# Sheet2.net
KiCad netlist of a schematic drawn in Altium Designer
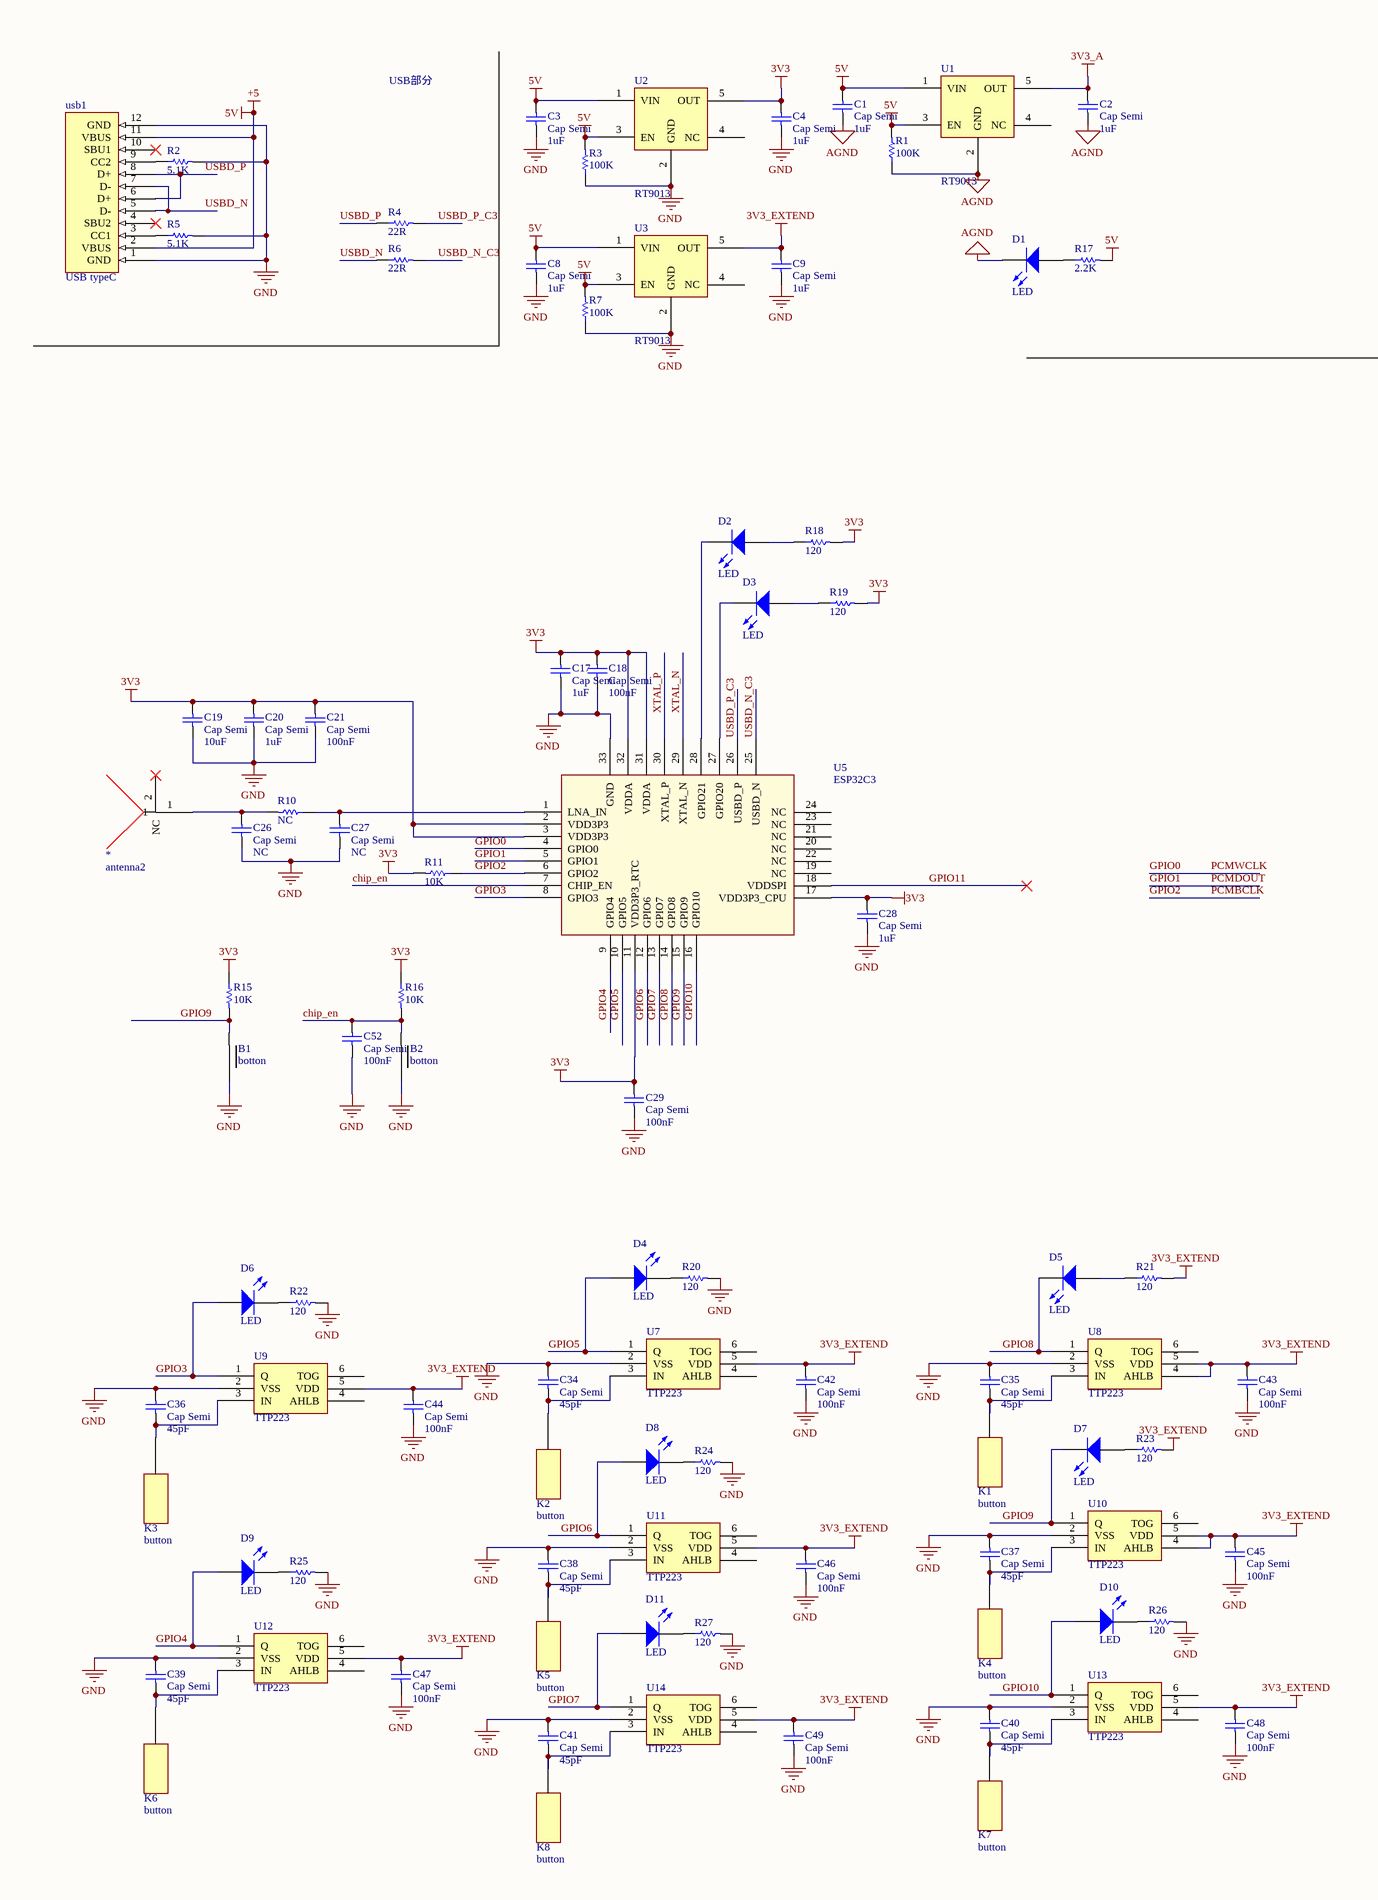
[diagram p0: Sheet2.SchDoc, left]
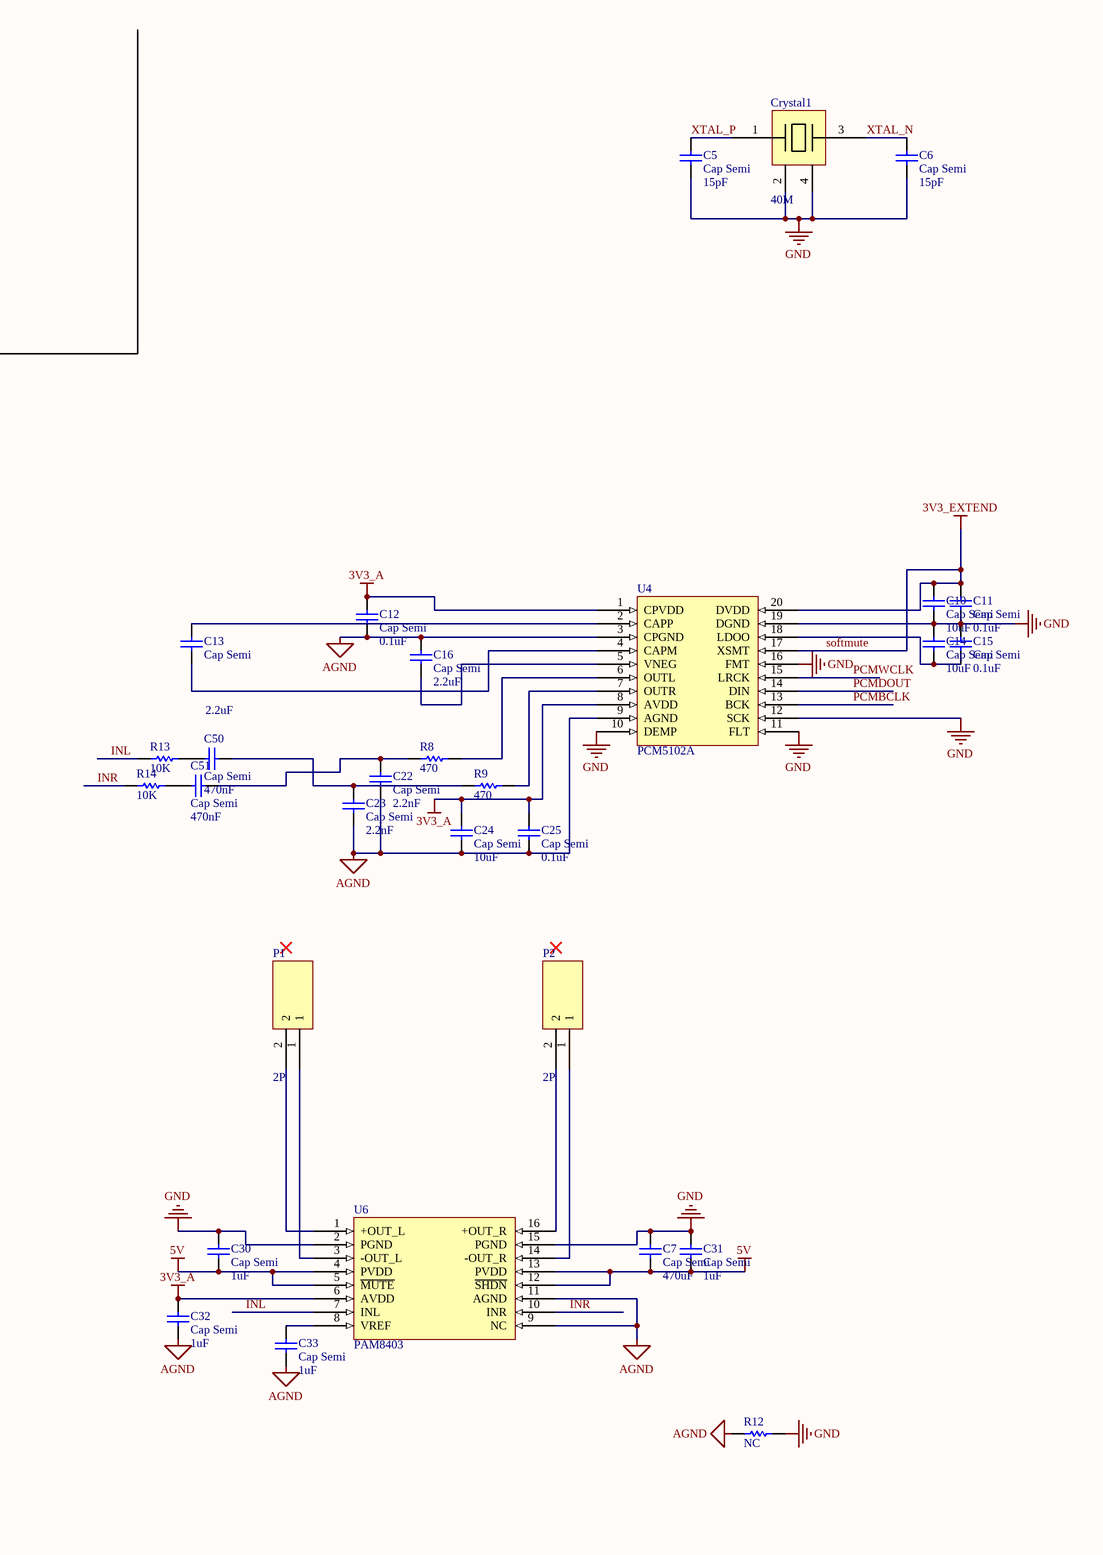
[diagram p1: Sheet2.SchDoc, right]

(export (version "E")
  (design (tool "Eeschema 10.0.6"))
  (components
    (comp (ref "*") (value "antenna2") (footprint "antana") (libsource (lib "lib_output") (part "antenna2")))
    (comp (ref "B1") (value "botton") (footprint "BOTTON_3*4") (libsource (lib "input") (part "botton")))
    (comp (ref "B2") (value "botton") (footprint "BOTTON_3*4") (libsource (lib "input") (part "botton")))
    (comp (ref "C1")
      (value "Cap Semi")
      (footprint "C1608[0603]")
      (description "Capacitor (Semiconductor SIM Model)")
      (fields (field (name "ALTIUM_VALUE") "1uF") (field (name "PUBLISHER") "Altium Limited"))
      (libsource (lib "common") (part "Cap Semi"))
    )
    (comp (ref "C2")
      (value "Cap Semi")
      (footprint "C1608[0603]")
      (description "Capacitor (Semiconductor SIM Model)")
      (fields (field (name "ALTIUM_VALUE") "1uF") (field (name "PUBLISHER") "Altium Limited"))
      (libsource (lib "common") (part "Cap Semi"))
    )
    (comp (ref "C3")
      (value "Cap Semi")
      (footprint "C1608[0603]")
      (description "Capacitor (Semiconductor SIM Model)")
      (fields (field (name "ALTIUM_VALUE") "1uF") (field (name "PUBLISHER") "Altium Limited"))
      (libsource (lib "common") (part "Cap Semi"))
    )
    (comp (ref "C4")
      (value "Cap Semi")
      (footprint "C1608[0603]")
      (description "Capacitor (Semiconductor SIM Model)")
      (fields (field (name "ALTIUM_VALUE") "1uF") (field (name "PUBLISHER") "Altium Limited"))
      (libsource (lib "common") (part "Cap Semi"))
    )
    (comp (ref "C5")
      (value "Cap Semi")
      (footprint "C1608[0603]")
      (description "Capacitor (Semiconductor SIM Model)")
      (fields (field (name "ALTIUM_VALUE") "15pF") (field (name "PUBLISHER") "Altium Limited"))
      (libsource (lib "common") (part "Cap Semi"))
    )
    (comp (ref "C6")
      (value "Cap Semi")
      (footprint "C1608[0603]")
      (description "Capacitor (Semiconductor SIM Model)")
      (fields (field (name "ALTIUM_VALUE") "15pF") (field (name "PUBLISHER") "Altium Limited"))
      (libsource (lib "common") (part "Cap Semi"))
    )
    (comp (ref "C7")
      (value "Cap Semi")
      (footprint "C1206")
      (description "Capacitor (Semiconductor SIM Model)")
      (fields (field (name "ALTIUM_VALUE") "470uF") (field (name "PUBLISHER") "Altium Limited"))
      (libsource (lib "common") (part "Cap Semi"))
    )
    (comp (ref "C8")
      (value "Cap Semi")
      (footprint "C1608[0603]")
      (description "Capacitor (Semiconductor SIM Model)")
      (fields (field (name "ALTIUM_VALUE") "1uF") (field (name "PUBLISHER") "Altium Limited"))
      (libsource (lib "common") (part "Cap Semi"))
    )
    (comp (ref "C9")
      (value "Cap Semi")
      (footprint "C1608[0603]")
      (description "Capacitor (Semiconductor SIM Model)")
      (fields (field (name "ALTIUM_VALUE") "1uF") (field (name "PUBLISHER") "Altium Limited"))
      (libsource (lib "common") (part "Cap Semi"))
    )
    (comp (ref "C10")
      (value "Cap Semi")
      (footprint "C1608[0603]")
      (description "Capacitor (Semiconductor SIM Model)")
      (fields (field (name "ALTIUM_VALUE") "10uF") (field (name "PUBLISHER") "Altium Limited"))
      (libsource (lib "common") (part "Cap Semi"))
    )
    (comp (ref "C11")
      (value "Cap Semi")
      (footprint "C1608[0603]")
      (description "Capacitor (Semiconductor SIM Model)")
      (fields (field (name "ALTIUM_VALUE") "0.1uF") (field (name "PUBLISHER") "Altium Limited"))
      (libsource (lib "common") (part "Cap Semi"))
    )
    (comp (ref "C12")
      (value "Cap Semi")
      (footprint "C1608[0603]")
      (description "Capacitor (Semiconductor SIM Model)")
      (fields (field (name "ALTIUM_VALUE") "0.1uF") (field (name "PUBLISHER") "Altium Limited"))
      (libsource (lib "common") (part "Cap Semi"))
    )
    (comp (ref "C13")
      (value "Cap Semi")
      (footprint "C1608[0603]")
      (description "Capacitor (Semiconductor SIM Model)")
      (fields (field (name "ALTIUM_VALUE") "2.2uF") (field (name "PUBLISHER") "Altium Limited"))
      (libsource (lib "common") (part "Cap Semi"))
    )
    (comp (ref "C14")
      (value "Cap Semi")
      (footprint "C1608[0603]")
      (description "Capacitor (Semiconductor SIM Model)")
      (fields (field (name "ALTIUM_VALUE") "10uF") (field (name "PUBLISHER") "Altium Limited"))
      (libsource (lib "common") (part "Cap Semi"))
    )
    (comp (ref "C15")
      (value "Cap Semi")
      (footprint "C1608[0603]")
      (description "Capacitor (Semiconductor SIM Model)")
      (fields (field (name "ALTIUM_VALUE") "0.1uF") (field (name "PUBLISHER") "Altium Limited"))
      (libsource (lib "common") (part "Cap Semi"))
    )
    (comp (ref "C16")
      (value "Cap Semi")
      (footprint "C1608[0603]")
      (description "Capacitor (Semiconductor SIM Model)")
      (fields (field (name "ALTIUM_VALUE") "2.2uF") (field (name "PUBLISHER") "Altium Limited"))
      (libsource (lib "common") (part "Cap Semi"))
    )
    (comp (ref "C17")
      (value "Cap Semi")
      (footprint "C1608[0603]")
      (description "Capacitor (Semiconductor SIM Model)")
      (fields (field (name "ALTIUM_VALUE") "1uF") (field (name "PUBLISHER") "Altium Limited"))
      (libsource (lib "common") (part "Cap Semi"))
    )
    (comp (ref "C18")
      (value "Cap Semi")
      (footprint "C1608[0603]")
      (description "Capacitor (Semiconductor SIM Model)")
      (fields (field (name "ALTIUM_VALUE") "100nF") (field (name "PUBLISHER") "Altium Limited"))
      (libsource (lib "common") (part "Cap Semi"))
    )
    (comp (ref "C19")
      (value "Cap Semi")
      (footprint "C0805")
      (description "Capacitor (Semiconductor SIM Model)")
      (fields (field (name "ALTIUM_VALUE") "10uF") (field (name "PUBLISHER") "Altium Limited"))
      (libsource (lib "common") (part "Cap Semi"))
    )
    (comp (ref "C20")
      (value "Cap Semi")
      (footprint "C1608[0603]")
      (description "Capacitor (Semiconductor SIM Model)")
      (fields (field (name "ALTIUM_VALUE") "1uF") (field (name "PUBLISHER") "Altium Limited"))
      (libsource (lib "common") (part "Cap Semi"))
    )
    (comp (ref "C21")
      (value "Cap Semi")
      (footprint "C1608[0603]")
      (description "Capacitor (Semiconductor SIM Model)")
      (fields (field (name "ALTIUM_VALUE") "100nF") (field (name "PUBLISHER") "Altium Limited"))
      (libsource (lib "common") (part "Cap Semi"))
    )
    (comp (ref "C22")
      (value "Cap Semi")
      (footprint "C1608[0603]")
      (description "Capacitor (Semiconductor SIM Model)")
      (fields (field (name "ALTIUM_VALUE") "2.2nF") (field (name "PUBLISHER") "Altium Limited"))
      (libsource (lib "common") (part "Cap Semi"))
    )
    (comp (ref "C23")
      (value "Cap Semi")
      (footprint "C1608[0603]")
      (description "Capacitor (Semiconductor SIM Model)")
      (fields (field (name "ALTIUM_VALUE") "2.2nF") (field (name "PUBLISHER") "Altium Limited"))
      (libsource (lib "common") (part "Cap Semi"))
    )
    (comp (ref "C24")
      (value "Cap Semi")
      (footprint "C1608[0603]")
      (description "Capacitor (Semiconductor SIM Model)")
      (fields (field (name "ALTIUM_VALUE") "10uF") (field (name "PUBLISHER") "Altium Limited"))
      (libsource (lib "common") (part "Cap Semi"))
    )
    (comp (ref "C25")
      (value "Cap Semi")
      (footprint "C1608[0603]")
      (description "Capacitor (Semiconductor SIM Model)")
      (fields (field (name "ALTIUM_VALUE") "0.1uF") (field (name "PUBLISHER") "Altium Limited"))
      (libsource (lib "common") (part "Cap Semi"))
    )
    (comp (ref "C26")
      (value "Cap Semi")
      (footprint "C1608[0603]")
      (description "Capacitor (Semiconductor SIM Model)")
      (fields (field (name "ALTIUM_VALUE") "NC") (field (name "PUBLISHER") "Altium Limited"))
      (libsource (lib "common") (part "Cap Semi"))
    )
    (comp (ref "C27")
      (value "Cap Semi")
      (footprint "C1608[0603]")
      (description "Capacitor (Semiconductor SIM Model)")
      (fields (field (name "ALTIUM_VALUE") "NC") (field (name "PUBLISHER") "Altium Limited"))
      (libsource (lib "common") (part "Cap Semi"))
    )
    (comp (ref "C28")
      (value "Cap Semi")
      (footprint "C1608[0603]")
      (description "Capacitor (Semiconductor SIM Model)")
      (fields (field (name "ALTIUM_VALUE") "1uF") (field (name "PUBLISHER") "Altium Limited"))
      (libsource (lib "common") (part "Cap Semi"))
    )
    (comp (ref "C29")
      (value "Cap Semi")
      (footprint "C1608[0603]")
      (description "Capacitor (Semiconductor SIM Model)")
      (fields (field (name "ALTIUM_VALUE") "100nF") (field (name "PUBLISHER") "Altium Limited"))
      (libsource (lib "common") (part "Cap Semi"))
    )
    (comp (ref "C30")
      (value "Cap Semi")
      (footprint "C1608[0603]")
      (description "Capacitor (Semiconductor SIM Model)")
      (fields (field (name "ALTIUM_VALUE") "1uF") (field (name "PUBLISHER") "Altium Limited"))
      (libsource (lib "common") (part "Cap Semi"))
    )
    (comp (ref "C31")
      (value "Cap Semi")
      (footprint "C1608[0603]")
      (description "Capacitor (Semiconductor SIM Model)")
      (fields (field (name "ALTIUM_VALUE") "1uF") (field (name "PUBLISHER") "Altium Limited"))
      (libsource (lib "common") (part "Cap Semi"))
    )
    (comp (ref "C32")
      (value "Cap Semi")
      (footprint "C1608[0603]")
      (description "Capacitor (Semiconductor SIM Model)")
      (fields (field (name "ALTIUM_VALUE") "1uF") (field (name "PUBLISHER") "Altium Limited"))
      (libsource (lib "common") (part "Cap Semi"))
    )
    (comp (ref "C33")
      (value "Cap Semi")
      (footprint "C1608[0603]")
      (description "Capacitor (Semiconductor SIM Model)")
      (fields (field (name "ALTIUM_VALUE") "1uF") (field (name "PUBLISHER") "Altium Limited"))
      (libsource (lib "common") (part "Cap Semi"))
    )
    (comp (ref "C34")
      (value "Cap Semi")
      (footprint "C1608[0603]")
      (description "Capacitor (Semiconductor SIM Model)")
      (fields (field (name "ALTIUM_VALUE") "45pF") (field (name "PUBLISHER") "Altium Limited"))
      (libsource (lib "common") (part "Cap Semi"))
    )
    (comp (ref "C35")
      (value "Cap Semi")
      (footprint "C1608[0603]")
      (description "Capacitor (Semiconductor SIM Model)")
      (fields (field (name "ALTIUM_VALUE") "45pF") (field (name "PUBLISHER") "Altium Limited"))
      (libsource (lib "common") (part "Cap Semi"))
    )
    (comp (ref "C36")
      (value "Cap Semi")
      (footprint "C1608[0603]")
      (description "Capacitor (Semiconductor SIM Model)")
      (fields (field (name "ALTIUM_VALUE") "45pF") (field (name "PUBLISHER") "Altium Limited"))
      (libsource (lib "common") (part "Cap Semi"))
    )
    (comp (ref "C37")
      (value "Cap Semi")
      (footprint "C1608[0603]")
      (description "Capacitor (Semiconductor SIM Model)")
      (fields (field (name "ALTIUM_VALUE") "45pF") (field (name "PUBLISHER") "Altium Limited"))
      (libsource (lib "common") (part "Cap Semi"))
    )
    (comp (ref "C38")
      (value "Cap Semi")
      (footprint "C1608[0603]")
      (description "Capacitor (Semiconductor SIM Model)")
      (fields (field (name "ALTIUM_VALUE") "45pF") (field (name "PUBLISHER") "Altium Limited"))
      (libsource (lib "common") (part "Cap Semi"))
    )
    (comp (ref "C39")
      (value "Cap Semi")
      (footprint "C1608[0603]")
      (description "Capacitor (Semiconductor SIM Model)")
      (fields (field (name "ALTIUM_VALUE") "45pF") (field (name "PUBLISHER") "Altium Limited"))
      (libsource (lib "common") (part "Cap Semi"))
    )
    (comp (ref "C40")
      (value "Cap Semi")
      (footprint "C1608[0603]")
      (description "Capacitor (Semiconductor SIM Model)")
      (fields (field (name "ALTIUM_VALUE") "45pF") (field (name "PUBLISHER") "Altium Limited"))
      (libsource (lib "common") (part "Cap Semi"))
    )
    (comp (ref "C41")
      (value "Cap Semi")
      (footprint "C1608[0603]")
      (description "Capacitor (Semiconductor SIM Model)")
      (fields (field (name "ALTIUM_VALUE") "45pF") (field (name "PUBLISHER") "Altium Limited"))
      (libsource (lib "common") (part "Cap Semi"))
    )
    (comp (ref "C42")
      (value "Cap Semi")
      (footprint "C1608[0603]")
      (description "Capacitor (Semiconductor SIM Model)")
      (fields (field (name "ALTIUM_VALUE") "100nF") (field (name "PUBLISHER") "Altium Limited"))
      (libsource (lib "common") (part "Cap Semi"))
    )
    (comp (ref "C43")
      (value "Cap Semi")
      (footprint "C1608[0603]")
      (description "Capacitor (Semiconductor SIM Model)")
      (fields (field (name "ALTIUM_VALUE") "100nF") (field (name "PUBLISHER") "Altium Limited"))
      (libsource (lib "common") (part "Cap Semi"))
    )
    (comp (ref "C44")
      (value "Cap Semi")
      (footprint "C1608[0603]")
      (description "Capacitor (Semiconductor SIM Model)")
      (fields (field (name "ALTIUM_VALUE") "100nF") (field (name "PUBLISHER") "Altium Limited"))
      (libsource (lib "common") (part "Cap Semi"))
    )
    (comp (ref "C45")
      (value "Cap Semi")
      (footprint "C1608[0603]")
      (description "Capacitor (Semiconductor SIM Model)")
      (fields (field (name "ALTIUM_VALUE") "100nF") (field (name "PUBLISHER") "Altium Limited"))
      (libsource (lib "common") (part "Cap Semi"))
    )
    (comp (ref "C46")
      (value "Cap Semi")
      (footprint "C1608[0603]")
      (description "Capacitor (Semiconductor SIM Model)")
      (fields (field (name "ALTIUM_VALUE") "100nF") (field (name "PUBLISHER") "Altium Limited"))
      (libsource (lib "common") (part "Cap Semi"))
    )
    (comp (ref "C47")
      (value "Cap Semi")
      (footprint "C1608[0603]")
      (description "Capacitor (Semiconductor SIM Model)")
      (fields (field (name "ALTIUM_VALUE") "100nF") (field (name "PUBLISHER") "Altium Limited"))
      (libsource (lib "common") (part "Cap Semi"))
    )
    (comp (ref "C48")
      (value "Cap Semi")
      (footprint "C1608[0603]")
      (description "Capacitor (Semiconductor SIM Model)")
      (fields (field (name "ALTIUM_VALUE") "100nF") (field (name "PUBLISHER") "Altium Limited"))
      (libsource (lib "common") (part "Cap Semi"))
    )
    (comp (ref "C49")
      (value "Cap Semi")
      (footprint "C1608[0603]")
      (description "Capacitor (Semiconductor SIM Model)")
      (fields (field (name "ALTIUM_VALUE") "100nF") (field (name "PUBLISHER") "Altium Limited"))
      (libsource (lib "common") (part "Cap Semi"))
    )
    (comp (ref "C50")
      (value "Cap Semi")
      (footprint "C1608[0603]")
      (description "Capacitor (Semiconductor SIM Model)")
      (fields (field (name "ALTIUM_VALUE") "470nF") (field (name "PUBLISHER") "Altium Limited"))
      (libsource (lib "common") (part "Cap Semi"))
    )
    (comp (ref "C51")
      (value "Cap Semi")
      (footprint "C1608[0603]")
      (description "Capacitor (Semiconductor SIM Model)")
      (fields (field (name "ALTIUM_VALUE") "470nF") (field (name "PUBLISHER") "Altium Limited"))
      (libsource (lib "common") (part "Cap Semi"))
    )
    (comp (ref "C52")
      (value "Cap Semi")
      (footprint "C1608[0603]")
      (description "Capacitor (Semiconductor SIM Model)")
      (fields (field (name "ALTIUM_VALUE") "100nF") (field (name "PUBLISHER") "Altium Limited"))
      (libsource (lib "common") (part "Cap Semi"))
    )
    (comp (ref "Crystal1")
      (value "40M")
      (footprint "3225 Crytsl")
      (libsource (lib "common") (part "Crytsl_4P"))
    )
    (comp (ref "D1")
      (value "LED")
      (footprint "LED_0805")
      (description "Typical INFRARED GaAs LED")
      (fields (field (name "PUBLISHER") "Altium Limited"))
      (libsource (lib "common") (part "LED"))
    )
    (comp (ref "D2")
      (value "LED")
      (footprint "LED_0805")
      (description "Typical INFRARED GaAs LED")
      (fields (field (name "PUBLISHER") "Altium Limited"))
      (libsource (lib "common") (part "LED"))
    )
    (comp (ref "D3")
      (value "LED")
      (footprint "LED_0805")
      (description "Typical INFRARED GaAs LED")
      (fields (field (name "PUBLISHER") "Altium Limited"))
      (libsource (lib "common") (part "LED"))
    )
    (comp (ref "D4")
      (value "LED")
      (footprint "LED_0805")
      (description "Typical INFRARED GaAs LED")
      (fields (field (name "PUBLISHER") "Altium Limited"))
      (libsource (lib "common") (part "LED"))
    )
    (comp (ref "D5")
      (value "LED")
      (footprint "LED_0805")
      (description "Typical INFRARED GaAs LED")
      (fields (field (name "PUBLISHER") "Altium Limited"))
      (libsource (lib "common") (part "LED"))
    )
    (comp (ref "D6")
      (value "LED")
      (footprint "LED_0805")
      (description "Typical INFRARED GaAs LED")
      (fields (field (name "PUBLISHER") "Altium Limited"))
      (libsource (lib "common") (part "LED"))
    )
    (comp (ref "D7")
      (value "LED")
      (footprint "LED_0805")
      (description "Typical INFRARED GaAs LED")
      (fields (field (name "PUBLISHER") "Altium Limited"))
      (libsource (lib "common") (part "LED"))
    )
    (comp (ref "D8")
      (value "LED")
      (footprint "LED_0805")
      (description "Typical INFRARED GaAs LED")
      (fields (field (name "PUBLISHER") "Altium Limited"))
      (libsource (lib "common") (part "LED"))
    )
    (comp (ref "D9")
      (value "LED")
      (footprint "LED_0805")
      (description "Typical INFRARED GaAs LED")
      (fields (field (name "PUBLISHER") "Altium Limited"))
      (libsource (lib "common") (part "LED"))
    )
    (comp (ref "D10")
      (value "LED")
      (footprint "LED_0805")
      (description "Typical INFRARED GaAs LED")
      (fields (field (name "PUBLISHER") "Altium Limited"))
      (libsource (lib "common") (part "LED"))
    )
    (comp (ref "D11")
      (value "LED")
      (footprint "LED_0805")
      (description "Typical INFRARED GaAs LED")
      (fields (field (name "PUBLISHER") "Altium Limited"))
      (libsource (lib "common") (part "LED"))
    )
    (comp (ref "K1")
      (value "button")
      (footprint "button_touch")
      (libsource (lib "input") (part "button_touch_square"))
    )
    (comp (ref "K2")
      (value "button")
      (footprint "button_touch")
      (libsource (lib "input") (part "button_touch_square"))
    )
    (comp (ref "K3")
      (value "button")
      (footprint "button_touch")
      (libsource (lib "input") (part "button_touch_square"))
    )
    (comp (ref "K4")
      (value "button")
      (footprint "button_touch")
      (libsource (lib "input") (part "button_touch_square"))
    )
    (comp (ref "K5")
      (value "button")
      (footprint "button_touch")
      (libsource (lib "input") (part "button_touch_square"))
    )
    (comp (ref "K6")
      (value "button")
      (footprint "button_touch")
      (libsource (lib "input") (part "button_touch_square"))
    )
    (comp (ref "K7")
      (value "button")
      (footprint "button_touch")
      (libsource (lib "input") (part "button_touch_square"))
    )
    (comp (ref "K8")
      (value "button")
      (footprint "button_touch")
      (libsource (lib "input") (part "button_touch_square"))
    )
    (comp (ref "P1") (value "2P") (footprint "2Px1.25") (libsource (lib "connector") (part "2P")))
    (comp (ref "P2") (value "2P") (footprint "2Px1.25") (libsource (lib "connector") (part "2P")))
    (comp (ref "R1")
      (value "100K")
      (footprint "R0603")
      (description "Semiconductor Resistor")
      (fields (field (name "Comment") "Res Semi") (field (name "PUBLISHER") "Altium Limited"))
      (libsource (lib "common") (part "Res Semi"))
    )
    (comp (ref "R2")
      (value "5.1K")
      (footprint "R0603")
      (description "Semiconductor Resistor")
      (fields (field (name "Comment") "Res Semi") (field (name "PUBLISHER") "Altium Limited"))
      (libsource (lib "common") (part "Res Semi"))
    )
    (comp (ref "R3")
      (value "100K")
      (footprint "R0603")
      (description "Semiconductor Resistor")
      (fields (field (name "Comment") "Res Semi") (field (name "PUBLISHER") "Altium Limited"))
      (libsource (lib "common") (part "Res Semi"))
    )
    (comp (ref "R4")
      (value "22R")
      (footprint "R0603")
      (description "Semiconductor Resistor")
      (fields (field (name "Comment") "Res Semi") (field (name "PUBLISHER") "Altium Limited"))
      (libsource (lib "common") (part "Res Semi"))
    )
    (comp (ref "R5")
      (value "5.1K")
      (footprint "R0603")
      (description "Semiconductor Resistor")
      (fields (field (name "Comment") "Res Semi") (field (name "PUBLISHER") "Altium Limited"))
      (libsource (lib "common") (part "Res Semi"))
    )
    (comp (ref "R6")
      (value "22R")
      (footprint "R0603")
      (description "Semiconductor Resistor")
      (fields (field (name "Comment") "Res Semi") (field (name "PUBLISHER") "Altium Limited"))
      (libsource (lib "common") (part "Res Semi"))
    )
    (comp (ref "R7")
      (value "100K")
      (footprint "R0603")
      (description "Semiconductor Resistor")
      (fields (field (name "Comment") "Res Semi") (field (name "PUBLISHER") "Altium Limited"))
      (libsource (lib "common") (part "Res Semi"))
    )
    (comp (ref "R8")
      (value "470")
      (footprint "R0603")
      (description "Semiconductor Resistor")
      (fields (field (name "Comment") "Res Semi") (field (name "PUBLISHER") "Altium Limited"))
      (libsource (lib "common") (part "Res Semi"))
    )
    (comp (ref "R9")
      (value "470")
      (footprint "R0603")
      (description "Semiconductor Resistor")
      (fields (field (name "Comment") "Res Semi") (field (name "PUBLISHER") "Altium Limited"))
      (libsource (lib "common") (part "Res Semi"))
    )
    (comp (ref "R10")
      (value "NC")
      (footprint "R0603")
      (description "Semiconductor Resistor")
      (fields (field (name "Comment") "Res Semi") (field (name "PUBLISHER") "Altium Limited"))
      (libsource (lib "common") (part "Res Semi"))
    )
    (comp (ref "R11")
      (value "10K")
      (footprint "R0603")
      (description "Semiconductor Resistor")
      (fields (field (name "Comment") "Res Semi") (field (name "PUBLISHER") "Altium Limited"))
      (libsource (lib "common") (part "Res Semi"))
    )
    (comp (ref "R12")
      (value "NC")
      (footprint "sigle_ground")
      (description "Semiconductor Resistor")
      (fields (field (name "Comment") "Res Semi") (field (name "PUBLISHER") "Altium Limited"))
      (libsource (lib "common") (part "Res Semi"))
    )
    (comp (ref "R13")
      (value "10K")
      (footprint "R0603")
      (description "Semiconductor Resistor")
      (fields (field (name "Comment") "Res Semi") (field (name "PUBLISHER") "Altium Limited"))
      (libsource (lib "common") (part "Res Semi"))
    )
    (comp (ref "R14")
      (value "10K")
      (footprint "R0603")
      (description "Semiconductor Resistor")
      (fields (field (name "Comment") "Res Semi") (field (name "PUBLISHER") "Altium Limited"))
      (libsource (lib "common") (part "Res Semi"))
    )
    (comp (ref "R15")
      (value "10K")
      (footprint "R0603")
      (description "Semiconductor Resistor")
      (fields (field (name "Comment") "Res Semi") (field (name "PUBLISHER") "Altium Limited"))
      (libsource (lib "common") (part "Res Semi"))
    )
    (comp (ref "R16")
      (value "10K")
      (footprint "R0603")
      (description "Semiconductor Resistor")
      (fields (field (name "Comment") "Res Semi") (field (name "PUBLISHER") "Altium Limited"))
      (libsource (lib "common") (part "Res Semi"))
    )
    (comp (ref "R17")
      (value "2.2K")
      (footprint "R0805")
      (description "Semiconductor Resistor")
      (fields (field (name "Comment") "Res Semi") (field (name "PUBLISHER") "Altium Limited"))
      (libsource (lib "common") (part "Res Semi"))
    )
    (comp (ref "R18")
      (value "120")
      (footprint "R0805")
      (description "Semiconductor Resistor")
      (fields (field (name "Comment") "Res Semi") (field (name "PUBLISHER") "Altium Limited"))
      (libsource (lib "common") (part "Res Semi"))
    )
    (comp (ref "R19")
      (value "120")
      (footprint "R0805")
      (description "Semiconductor Resistor")
      (fields (field (name "Comment") "Res Semi") (field (name "PUBLISHER") "Altium Limited"))
      (libsource (lib "common") (part "Res Semi"))
    )
    (comp (ref "R20")
      (value "120")
      (footprint "R0805")
      (description "Semiconductor Resistor")
      (fields (field (name "Comment") "Res Semi") (field (name "PUBLISHER") "Altium Limited"))
      (libsource (lib "common") (part "Res Semi"))
    )
    (comp (ref "R21")
      (value "120")
      (footprint "R0805")
      (description "Semiconductor Resistor")
      (fields (field (name "Comment") "Res Semi") (field (name "PUBLISHER") "Altium Limited"))
      (libsource (lib "common") (part "Res Semi"))
    )
    (comp (ref "R22")
      (value "120")
      (footprint "R0805")
      (description "Semiconductor Resistor")
      (fields (field (name "Comment") "Res Semi") (field (name "PUBLISHER") "Altium Limited"))
      (libsource (lib "common") (part "Res Semi"))
    )
    (comp (ref "R23")
      (value "120")
      (footprint "R0805")
      (description "Semiconductor Resistor")
      (fields (field (name "Comment") "Res Semi") (field (name "PUBLISHER") "Altium Limited"))
      (libsource (lib "common") (part "Res Semi"))
    )
    (comp (ref "R24")
      (value "120")
      (footprint "R0805")
      (description "Semiconductor Resistor")
      (fields (field (name "Comment") "Res Semi") (field (name "PUBLISHER") "Altium Limited"))
      (libsource (lib "common") (part "Res Semi"))
    )
    (comp (ref "R25")
      (value "120")
      (footprint "R0805")
      (description "Semiconductor Resistor")
      (fields (field (name "Comment") "Res Semi") (field (name "PUBLISHER") "Altium Limited"))
      (libsource (lib "common") (part "Res Semi"))
    )
    (comp (ref "R26")
      (value "120")
      (footprint "R0805")
      (description "Semiconductor Resistor")
      (fields (field (name "Comment") "Res Semi") (field (name "PUBLISHER") "Altium Limited"))
      (libsource (lib "common") (part "Res Semi"))
    )
    (comp (ref "R27")
      (value "120")
      (footprint "R0805")
      (description "Semiconductor Resistor")
      (fields (field (name "Comment") "Res Semi") (field (name "PUBLISHER") "Altium Limited"))
      (libsource (lib "common") (part "Res Semi"))
    )
    (comp (ref "U1") (value "RT9013") (footprint "SOT23-5") (libsource (lib "ic") (part "RT9013")))
    (comp (ref "U2") (value "RT9013") (footprint "SOT23-5") (libsource (lib "ic") (part "RT9013")))
    (comp (ref "U3") (value "RT9013") (footprint "SOT23-5") (libsource (lib "ic") (part "RT9013")))
    (comp (ref "U4") (value "PCM5102A") (footprint "TSSOP20") (libsource (lib "ic") (part "PCM5120A")))
    (comp (ref "U5") (value "ESP32C3") (footprint "QFN32 5x5_M") (libsource (lib "ic") (part "ESP32C3")))
    (comp (ref "U6") (value "PAM8403") (footprint "SOP16") (libsource (lib "ic") (part "PAM8403")))
    (comp (ref "U7") (value "TTP223") (footprint "SOT23-6") (libsource (lib "ic") (part "TTP223")))
    (comp (ref "U8") (value "TTP223") (footprint "SOT23-6") (libsource (lib "ic") (part "TTP223")))
    (comp (ref "U9") (value "TTP223") (footprint "SOT23-6") (libsource (lib "ic") (part "TTP223")))
    (comp (ref "U10") (value "TTP223") (footprint "SOT23-6") (libsource (lib "ic") (part "TTP223")))
    (comp (ref "U11") (value "TTP223") (footprint "SOT23-6") (libsource (lib "ic") (part "TTP223")))
    (comp (ref "U12") (value "TTP223") (footprint "SOT23-6") (libsource (lib "ic") (part "TTP223")))
    (comp (ref "U13") (value "TTP223") (footprint "SOT23-6") (libsource (lib "ic") (part "TTP223")))
    (comp (ref "U14") (value "TTP223") (footprint "SOT23-6") (libsource (lib "ic") (part "TTP223")))
    (comp (ref "usb1")
      (value "USB typeC")
      (footprint "USB typeC")
      (libsource (lib "input") (part "USB typeC"))
    )
  )
  (nets
    (net (code "1") (name "+5") (class "Default")
      (node (ref "C1") (pin "2") (pinfunction "2_2") (pintype "passive"))
      (node (ref "C3") (pin "2") (pinfunction "2_2") (pintype "passive"))
      (node (ref "C30") (pin "1") (pinfunction "1_1") (pintype "passive"))
      (node (ref "C31") (pin "1") (pinfunction "1_1") (pintype "passive"))
      (node (ref "C7") (pin "1") (pinfunction "1_1") (pintype "passive"))
      (node (ref "C8") (pin "2") (pinfunction "2_2") (pintype "passive"))
      (node (ref "R1") (pin "2") (pinfunction "2_2") (pintype "passive"))
      (node (ref "R17") (pin "2") (pinfunction "2_2") (pintype "passive"))
      (node (ref "R3") (pin "2") (pinfunction "2_2") (pintype "passive"))
      (node (ref "R7") (pin "2") (pinfunction "2_2") (pintype "passive"))
      (node (ref "U1") (pin "1") (pinfunction "VIN_1") (pintype "passive"))
      (node (ref "U1") (pin "3") (pinfunction "EN_3") (pintype "passive"))
      (node (ref "U2") (pin "1") (pinfunction "VIN_1") (pintype "passive"))
      (node (ref "U2") (pin "3") (pinfunction "EN_3") (pintype "passive"))
      (node (ref "U3") (pin "1") (pinfunction "VIN_1") (pintype "passive"))
      (node (ref "U3") (pin "3") (pinfunction "EN_3") (pintype "passive"))
      (node (ref "U6") (pin "12") (pinfunction "~{SHDN}_12") (pintype "input"))
      (node (ref "U6") (pin "13") (pinfunction "PVDD_13") (pintype "input"))
      (node (ref "U6") (pin "4") (pinfunction "PVDD_4") (pintype "input"))
      (node (ref "U6") (pin "5") (pinfunction "~{MUTE}_5") (pintype "input"))
      (node (ref "usb1") (pin "11") (pinfunction "VBUS_11") (pintype "input"))
      (node (ref "usb1") (pin "2") (pinfunction "VBUS_2") (pintype "input"))
    )
    (net (code "2") (name "/GPIO0") (class "Default")
      (node (ref "U4") (pin "15") (pinfunction "LRCK_15") (pintype "input"))
      (node (ref "U5") (pin "4") (pinfunction "GPIO0_4") (pintype "passive"))
    )
    (net (code "3") (name "/GPIO1") (class "Default")
      (node (ref "U4") (pin "14") (pinfunction "DIN_14") (pintype "input"))
      (node (ref "U5") (pin "5") (pinfunction "GPIO1_5") (pintype "passive"))
    )
    (net (code "4") (name "/GPIO2") (class "Default")
      (node (ref "R11") (pin "1") (pinfunction "1_1") (pintype "passive"))
      (node (ref "U4") (pin "13") (pinfunction "BCK_13") (pintype "input"))
      (node (ref "U5") (pin "6") (pinfunction "GPIO2_6") (pintype "passive"))
    )
    (net (code "5") (name "/GPIO3") (class "Default")
      (node (ref "D6") (pin "1") (pinfunction "A_1") (pintype "passive"))
      (node (ref "U5") (pin "8") (pinfunction "GPIO3_8") (pintype "passive"))
      (node (ref "U9") (pin "1") (pinfunction "Q_1") (pintype "passive"))
    )
    (net (code "6") (name "/GPIO4") (class "Default")
      (node (ref "D9") (pin "1") (pinfunction "A_1") (pintype "passive"))
      (node (ref "U12") (pin "1") (pinfunction "Q_1") (pintype "passive"))
      (node (ref "U5") (pin "9") (pinfunction "GPIO4_9") (pintype "passive"))
    )
    (net (code "7") (name "/GPIO5") (class "Default")
      (node (ref "D4") (pin "1") (pinfunction "A_1") (pintype "passive"))
      (node (ref "U5") (pin "10") (pinfunction "GPIO5_10") (pintype "passive"))
      (node (ref "U7") (pin "1") (pinfunction "Q_1") (pintype "passive"))
    )
    (net (code "8") (name "/GPIO6") (class "Default")
      (node (ref "D8") (pin "1") (pinfunction "A_1") (pintype "passive"))
      (node (ref "U11") (pin "1") (pinfunction "Q_1") (pintype "passive"))
      (node (ref "U5") (pin "12") (pinfunction "GPIO6_12") (pintype "passive"))
    )
    (net (code "9") (name "/GPIO7") (class "Default")
      (node (ref "D11") (pin "1") (pinfunction "A_1") (pintype "passive"))
      (node (ref "U14") (pin "1") (pinfunction "Q_1") (pintype "passive"))
      (node (ref "U5") (pin "13") (pinfunction "GPIO7_13") (pintype "passive"))
    )
    (net (code "10") (name "/GPIO8") (class "Default")
      (node (ref "D5") (pin "2") (pinfunction "K_2") (pintype "passive"))
      (node (ref "U5") (pin "14") (pinfunction "GPIO8_14") (pintype "passive"))
      (node (ref "U8") (pin "1") (pinfunction "Q_1") (pintype "passive"))
    )
    (net (code "11") (name "/GPIO9") (class "Default")
      (node (ref "B1") (pin "1") (pinfunction "1_1") (pintype "passive"))
      (node (ref "D7") (pin "2") (pinfunction "K_2") (pintype "passive"))
      (node (ref "R15") (pin "2") (pinfunction "2_2") (pintype "passive"))
      (node (ref "U10") (pin "1") (pinfunction "Q_1") (pintype "passive"))
      (node (ref "U5") (pin "15") (pinfunction "GPIO9_15") (pintype "passive"))
    )
    (net (code "12") (name "/GPIO10") (class "Default")
      (node (ref "D10") (pin "1") (pinfunction "A_1") (pintype "passive"))
      (node (ref "U13") (pin "1") (pinfunction "Q_1") (pintype "passive"))
      (node (ref "U5") (pin "16") (pinfunction "GPIO10_16") (pintype "passive"))
    )
    (net (code "13") (name "/GPIO11") (class "Default")
      (node (ref "U5") (pin "18") (pinfunction "VDDSPI_18") (pintype "passive+no_connect"))
    )
    (net (code "14") (name "/INL") (class "Default")
      (node (ref "R13") (pin "2") (pinfunction "2_2") (pintype "passive"))
      (node (ref "U6") (pin "7") (pinfunction "INL_7") (pintype "input"))
    )
    (net (code "15") (name "/INR") (class "Default")
      (node (ref "R14") (pin "2") (pinfunction "2_2") (pintype "passive"))
      (node (ref "U6") (pin "10") (pinfunction "INR_10") (pintype "input"))
    )
    (net (code "16") (name "/USBD_N") (class "Default")
      (node (ref "R6") (pin "1") (pinfunction "1_1") (pintype "passive"))
      (node (ref "usb1") (pin "5") (pinfunction "D-_5") (pintype "input"))
      (node (ref "usb1") (pin "7") (pinfunction "D-_7") (pintype "input"))
    )
    (net (code "17") (name "/USBD_N_C3") (class "Default")
      (node (ref "R6") (pin "2") (pinfunction "2_2") (pintype "passive"))
      (node (ref "U5") (pin "25") (pinfunction "USBD_N_25") (pintype "passive"))
    )
    (net (code "18") (name "/USBD_P") (class "Default")
      (node (ref "R4") (pin "1") (pinfunction "1_1") (pintype "passive"))
      (node (ref "usb1") (pin "6") (pinfunction "D+_6") (pintype "input"))
      (node (ref "usb1") (pin "8") (pinfunction "D+_8") (pintype "input"))
    )
    (net (code "19") (name "/USBD_P_C3") (class "Default")
      (node (ref "R4") (pin "2") (pinfunction "2_2") (pintype "passive"))
      (node (ref "U5") (pin "26") (pinfunction "USBD_P_26") (pintype "passive"))
    )
    (net (code "20") (name "/XTAL_N") (class "Default")
      (node (ref "C6") (pin "2") (pinfunction "2_2") (pintype "passive"))
      (node (ref "Crystal1") (pin "3") (pinfunction "3_3") (pintype "passive"))
      (node (ref "U5") (pin "29") (pinfunction "XTAL_N_29") (pintype "passive"))
    )
    (net (code "21") (name "/XTAL_P") (class "Default")
      (node (ref "C5") (pin "2") (pinfunction "2_2") (pintype "passive"))
      (node (ref "Crystal1") (pin "1") (pinfunction "1_1") (pintype "passive"))
      (node (ref "U5") (pin "30") (pinfunction "XTAL_P_30") (pintype "passive"))
    )
    (net (code "22") (name "/chip_en") (class "Default")
      (node (ref "B2") (pin "1") (pinfunction "1_1") (pintype "passive"))
      (node (ref "C52") (pin "2") (pinfunction "2_2") (pintype "passive"))
      (node (ref "R16") (pin "2") (pinfunction "2_2") (pintype "passive"))
      (node (ref "U5") (pin "7") (pinfunction "CHIP_EN_7") (pintype "passive"))
    )
    (net (code "23") (name "3V3") (class "Default")
      (node (ref "C17") (pin "2") (pinfunction "2_2") (pintype "passive"))
      (node (ref "C18") (pin "2") (pinfunction "2_2") (pintype "passive"))
      (node (ref "C19") (pin "2") (pinfunction "2_2") (pintype "passive"))
      (node (ref "C20") (pin "2") (pinfunction "2_2") (pintype "passive"))
      (node (ref "C21") (pin "2") (pinfunction "2_2") (pintype "passive"))
      (node (ref "C28") (pin "2") (pinfunction "2_2") (pintype "passive"))
      (node (ref "C29") (pin "2") (pinfunction "2_2") (pintype "passive"))
      (node (ref "C4") (pin "2") (pinfunction "2_2") (pintype "passive"))
      (node (ref "R11") (pin "2") (pinfunction "2_2") (pintype "passive"))
      (node (ref "R15") (pin "1") (pinfunction "1_1") (pintype "passive"))
      (node (ref "R16") (pin "1") (pinfunction "1_1") (pintype "passive"))
      (node (ref "R18") (pin "2") (pinfunction "2_2") (pintype "passive"))
      (node (ref "R19") (pin "2") (pinfunction "2_2") (pintype "passive"))
      (node (ref "U2") (pin "5") (pinfunction "OUT_5") (pintype "passive"))
      (node (ref "U5") (pin "11") (pinfunction "VDD3P3_RTC_11") (pintype "passive"))
      (node (ref "U5") (pin "17") (pinfunction "VDD3P3_CPU_17") (pintype "passive"))
      (node (ref "U5") (pin "2") (pinfunction "VDD3P3_2") (pintype "passive"))
      (node (ref "U5") (pin "3") (pinfunction "VDD3P3_3") (pintype "passive"))
      (node (ref "U5") (pin "31") (pinfunction "VDDA_31") (pintype "passive"))
      (node (ref "U5") (pin "32") (pinfunction "VDDA_32") (pintype "passive"))
    )
    (net (code "24") (name "3V3_A") (class "Default")
      (node (ref "C12") (pin "2") (pinfunction "2_2") (pintype "passive"))
      (node (ref "C2") (pin "2") (pinfunction "2_2") (pintype "passive"))
      (node (ref "C24") (pin "2") (pinfunction "2_2") (pintype "passive"))
      (node (ref "C25") (pin "2") (pinfunction "2_2") (pintype "passive"))
      (node (ref "C32") (pin "2") (pinfunction "2_2") (pintype "passive"))
      (node (ref "U1") (pin "5") (pinfunction "OUT_5") (pintype "passive"))
      (node (ref "U4") (pin "1") (pinfunction "CPVDD_1") (pintype "input"))
      (node (ref "U4") (pin "8") (pinfunction "AVDD_8") (pintype "input"))
      (node (ref "U6") (pin "6") (pinfunction "AVDD_6") (pintype "input"))
    )
    (net (code "25") (name "3V3_EXTEND") (class "Default")
      (node (ref "C10") (pin "2") (pinfunction "2_2") (pintype "passive"))
      (node (ref "C11") (pin "2") (pinfunction "2_2") (pintype "passive"))
      (node (ref "C42") (pin "2") (pinfunction "2_2") (pintype "passive"))
      (node (ref "C43") (pin "2") (pinfunction "2_2") (pintype "passive"))
      (node (ref "C44") (pin "2") (pinfunction "2_2") (pintype "passive"))
      (node (ref "C45") (pin "2") (pinfunction "2_2") (pintype "passive"))
      (node (ref "C46") (pin "2") (pinfunction "2_2") (pintype "passive"))
      (node (ref "C47") (pin "2") (pinfunction "2_2") (pintype "passive"))
      (node (ref "C48") (pin "2") (pinfunction "2_2") (pintype "passive"))
      (node (ref "C49") (pin "2") (pinfunction "2_2") (pintype "passive"))
      (node (ref "C9") (pin "2") (pinfunction "2_2") (pintype "passive"))
      (node (ref "R21") (pin "2") (pinfunction "2_2") (pintype "passive"))
      (node (ref "R23") (pin "2") (pinfunction "2_2") (pintype "passive"))
      (node (ref "U10") (pin "4") (pinfunction "AHLB_4") (pintype "passive"))
      (node (ref "U10") (pin "5") (pinfunction "VDD_5") (pintype "passive"))
      (node (ref "U11") (pin "5") (pinfunction "VDD_5") (pintype "passive"))
      (node (ref "U12") (pin "5") (pinfunction "VDD_5") (pintype "passive"))
      (node (ref "U13") (pin "5") (pinfunction "VDD_5") (pintype "passive"))
      (node (ref "U14") (pin "5") (pinfunction "VDD_5") (pintype "passive"))
      (node (ref "U3") (pin "5") (pinfunction "OUT_5") (pintype "passive"))
      (node (ref "U4") (pin "17") (pinfunction "XSMT_17") (pintype "input"))
      (node (ref "U4") (pin "20") (pinfunction "DVDD_20") (pintype "input"))
      (node (ref "U7") (pin "5") (pinfunction "VDD_5") (pintype "passive"))
      (node (ref "U8") (pin "4") (pinfunction "AHLB_4") (pintype "passive"))
      (node (ref "U8") (pin "5") (pinfunction "VDD_5") (pintype "passive"))
      (node (ref "U9") (pin "5") (pinfunction "VDD_5") (pintype "passive"))
    )
    (net (code "26") (name "AGND") (class "Default")
      (node (ref "C1") (pin "1") (pinfunction "1_1") (pintype "passive"))
      (node (ref "C12") (pin "1") (pinfunction "1_1") (pintype "passive"))
      (node (ref "C16") (pin "2") (pinfunction "2_2") (pintype "passive"))
      (node (ref "C2") (pin "1") (pinfunction "1_1") (pintype "passive"))
      (node (ref "C22") (pin "1") (pinfunction "1_1") (pintype "passive"))
      (node (ref "C23") (pin "1") (pinfunction "1_1") (pintype "passive"))
      (node (ref "C24") (pin "1") (pinfunction "1_1") (pintype "passive"))
      (node (ref "C25") (pin "1") (pinfunction "1_1") (pintype "passive"))
      (node (ref "C32") (pin "1") (pinfunction "1_1") (pintype "passive"))
      (node (ref "C33") (pin "1") (pinfunction "1_1") (pintype "passive"))
      (node (ref "D1") (pin "2") (pinfunction "K_2") (pintype "passive"))
      (node (ref "R1") (pin "1") (pinfunction "1_1") (pintype "passive"))
      (node (ref "R12") (pin "1") (pinfunction "1_1") (pintype "passive"))
      (node (ref "U1") (pin "2") (pinfunction "GND_2") (pintype "passive"))
      (node (ref "U4") (pin "3") (pinfunction "CPGND_3") (pintype "input"))
      (node (ref "U4") (pin "9") (pinfunction "AGND_9") (pintype "input"))
      (node (ref "U6") (pin "11") (pinfunction "AGND_11") (pintype "input"))
      (node (ref "U6") (pin "9") (pinfunction "NC_9") (pintype "input"))
    )
    (net (code "27") (name "GND") (class "Default")
      (node (ref "B1") (pin "4") (pinfunction "4_4") (pintype "passive"))
      (node (ref "B2") (pin "4") (pinfunction "4_4") (pintype "passive"))
      (node (ref "C10") (pin "1") (pinfunction "1_1") (pintype "passive"))
      (node (ref "C11") (pin "1") (pinfunction "1_1") (pintype "passive"))
      (node (ref "C14") (pin "2") (pinfunction "2_2") (pintype "passive"))
      (node (ref "C15") (pin "2") (pinfunction "2_2") (pintype "passive"))
      (node (ref "C17") (pin "1") (pinfunction "1_1") (pintype "passive"))
      (node (ref "C18") (pin "1") (pinfunction "1_1") (pintype "passive"))
      (node (ref "C19") (pin "1") (pinfunction "1_1") (pintype "passive"))
      (node (ref "C20") (pin "1") (pinfunction "1_1") (pintype "passive"))
      (node (ref "C21") (pin "1") (pinfunction "1_1") (pintype "passive"))
      (node (ref "C26") (pin "1") (pinfunction "1_1") (pintype "passive"))
      (node (ref "C27") (pin "1") (pinfunction "1_1") (pintype "passive"))
      (node (ref "C28") (pin "1") (pinfunction "1_1") (pintype "passive"))
      (node (ref "C29") (pin "1") (pinfunction "1_1") (pintype "passive"))
      (node (ref "C3") (pin "1") (pinfunction "1_1") (pintype "passive"))
      (node (ref "C30") (pin "2") (pinfunction "2_2") (pintype "passive"))
      (node (ref "C31") (pin "2") (pinfunction "2_2") (pintype "passive"))
      (node (ref "C34") (pin "2") (pinfunction "2_2") (pintype "passive"))
      (node (ref "C35") (pin "2") (pinfunction "2_2") (pintype "passive"))
      (node (ref "C36") (pin "2") (pinfunction "2_2") (pintype "passive"))
      (node (ref "C37") (pin "2") (pinfunction "2_2") (pintype "passive"))
      (node (ref "C38") (pin "2") (pinfunction "2_2") (pintype "passive"))
      (node (ref "C39") (pin "2") (pinfunction "2_2") (pintype "passive"))
      (node (ref "C4") (pin "1") (pinfunction "1_1") (pintype "passive"))
      (node (ref "C40") (pin "2") (pinfunction "2_2") (pintype "passive"))
      (node (ref "C41") (pin "2") (pinfunction "2_2") (pintype "passive"))
      (node (ref "C42") (pin "1") (pinfunction "1_1") (pintype "passive"))
      (node (ref "C43") (pin "1") (pinfunction "1_1") (pintype "passive"))
      (node (ref "C44") (pin "1") (pinfunction "1_1") (pintype "passive"))
      (node (ref "C45") (pin "1") (pinfunction "1_1") (pintype "passive"))
      (node (ref "C46") (pin "1") (pinfunction "1_1") (pintype "passive"))
      (node (ref "C47") (pin "1") (pinfunction "1_1") (pintype "passive"))
      (node (ref "C48") (pin "1") (pinfunction "1_1") (pintype "passive"))
      (node (ref "C49") (pin "1") (pinfunction "1_1") (pintype "passive"))
      (node (ref "C5") (pin "1") (pinfunction "1_1") (pintype "passive"))
      (node (ref "C52") (pin "1") (pinfunction "1_1") (pintype "passive"))
      (node (ref "C6") (pin "1") (pinfunction "1_1") (pintype "passive"))
      (node (ref "C7") (pin "2") (pinfunction "2_2") (pintype "passive"))
      (node (ref "C8") (pin "1") (pinfunction "1_1") (pintype "passive"))
      (node (ref "C9") (pin "1") (pinfunction "1_1") (pintype "passive"))
      (node (ref "Crystal1") (pin "2") (pinfunction "2_2") (pintype "passive"))
      (node (ref "Crystal1") (pin "4") (pinfunction "4_4") (pintype "passive"))
      (node (ref "R12") (pin "2") (pinfunction "2_2") (pintype "passive"))
      (node (ref "R2") (pin "2") (pinfunction "2_2") (pintype "passive"))
      (node (ref "R20") (pin "2") (pinfunction "2_2") (pintype "passive"))
      (node (ref "R22") (pin "2") (pinfunction "2_2") (pintype "passive"))
      (node (ref "R24") (pin "2") (pinfunction "2_2") (pintype "passive"))
      (node (ref "R25") (pin "2") (pinfunction "2_2") (pintype "passive"))
      (node (ref "R26") (pin "2") (pinfunction "2_2") (pintype "passive"))
      (node (ref "R27") (pin "2") (pinfunction "2_2") (pintype "passive"))
      (node (ref "R3") (pin "1") (pinfunction "1_1") (pintype "passive"))
      (node (ref "R5") (pin "2") (pinfunction "2_2") (pintype "passive"))
      (node (ref "R7") (pin "1") (pinfunction "1_1") (pintype "passive"))
      (node (ref "U10") (pin "2") (pinfunction "VSS_2") (pintype "passive"))
      (node (ref "U11") (pin "2") (pinfunction "VSS_2") (pintype "passive"))
      (node (ref "U12") (pin "2") (pinfunction "VSS_2") (pintype "passive"))
      (node (ref "U13") (pin "2") (pinfunction "VSS_2") (pintype "passive"))
      (node (ref "U14") (pin "2") (pinfunction "VSS_2") (pintype "passive"))
      (node (ref "U2") (pin "2") (pinfunction "GND_2") (pintype "passive"))
      (node (ref "U3") (pin "2") (pinfunction "GND_2") (pintype "passive"))
      (node (ref "U4") (pin "10") (pinfunction "DEMP_10") (pintype "input"))
      (node (ref "U4") (pin "11") (pinfunction "FLT_11") (pintype "input"))
      (node (ref "U4") (pin "12") (pinfunction "SCK_12") (pintype "input"))
      (node (ref "U4") (pin "16") (pinfunction "FMT_16") (pintype "input"))
      (node (ref "U4") (pin "19") (pinfunction "DGND_19") (pintype "input"))
      (node (ref "U5") (pin "33") (pinfunction "GND_33") (pintype "passive"))
      (node (ref "U6") (pin "15") (pinfunction "PGND_15") (pintype "input"))
      (node (ref "U6") (pin "2") (pinfunction "PGND_2") (pintype "input"))
      (node (ref "U7") (pin "2") (pinfunction "VSS_2") (pintype "passive"))
      (node (ref "U8") (pin "2") (pinfunction "VSS_2") (pintype "passive"))
      (node (ref "U9") (pin "2") (pinfunction "VSS_2") (pintype "passive"))
      (node (ref "usb1") (pin "1") (pinfunction "GND_1") (pintype "input"))
      (node (ref "usb1") (pin "12") (pinfunction "GND_12") (pintype "input"))
    )
    (net (code "28") (name "Net-(*-Pad1)") (class "Default")
      (node (ref "*") (pin "1") (pinfunction "1_1") (pintype "passive"))
      (node (ref "C26") (pin "2") (pinfunction "2_2") (pintype "passive"))
      (node (ref "R10") (pin "2") (pinfunction "2_2") (pintype "passive"))
    )
    (net (code "29") (name "Net-(C22-Pad2)") (class "Default")
      (node (ref "C22") (pin "2") (pinfunction "2_2") (pintype "passive"))
      (node (ref "C51") (pin "2") (pinfunction "2_2") (pintype "passive"))
      (node (ref "R8") (pin "2") (pinfunction "2_2") (pintype "passive"))
    )
    (net (code "30") (name "Net-(C23-Pad2)") (class "Default")
      (node (ref "C23") (pin "2") (pinfunction "2_2") (pintype "passive"))
      (node (ref "C50") (pin "2") (pinfunction "2_2") (pintype "passive"))
      (node (ref "R9") (pin "2") (pinfunction "2_2") (pintype "passive"))
    )
    (net (code "31") (name "Net-(C50-Pad1)") (class "Default")
      (node (ref "C50") (pin "1") (pinfunction "1_1") (pintype "passive"))
      (node (ref "R13") (pin "1") (pinfunction "1_1") (pintype "passive"))
    )
    (net (code "32") (name "Net-(C51-Pad1)") (class "Default")
      (node (ref "C51") (pin "1") (pinfunction "1_1") (pintype "passive"))
      (node (ref "R14") (pin "1") (pinfunction "1_1") (pintype "passive"))
    )
    (net (code "33") (name "Net-(D1-A)") (class "Default")
      (node (ref "D1") (pin "1") (pinfunction "A_1") (pintype "passive"))
      (node (ref "R17") (pin "1") (pinfunction "1_1") (pintype "passive"))
    )
    (net (code "34") (name "Net-(D2-A)") (class "Default")
      (node (ref "D2") (pin "1") (pinfunction "A_1") (pintype "passive"))
      (node (ref "R18") (pin "1") (pinfunction "1_1") (pintype "passive"))
    )
    (net (code "35") (name "Net-(D2-K)") (class "Default")
      (node (ref "D2") (pin "2") (pinfunction "K_2") (pintype "passive"))
      (node (ref "U5") (pin "28") (pinfunction "GPIO21_28") (pintype "passive"))
    )
    (net (code "36") (name "Net-(D3-A)") (class "Default")
      (node (ref "D3") (pin "1") (pinfunction "A_1") (pintype "passive"))
      (node (ref "R19") (pin "1") (pinfunction "1_1") (pintype "passive"))
    )
    (net (code "37") (name "Net-(D3-K)") (class "Default")
      (node (ref "D3") (pin "2") (pinfunction "K_2") (pintype "passive"))
      (node (ref "U5") (pin "27") (pinfunction "GPIO20_27") (pintype "passive"))
    )
    (net (code "38") (name "Net-(D4-K)") (class "Default")
      (node (ref "D4") (pin "2") (pinfunction "K_2") (pintype "passive"))
      (node (ref "R20") (pin "1") (pinfunction "1_1") (pintype "passive"))
    )
    (net (code "39") (name "Net-(D5-A)") (class "Default")
      (node (ref "D5") (pin "1") (pinfunction "A_1") (pintype "passive"))
      (node (ref "R21") (pin "1") (pinfunction "1_1") (pintype "passive"))
    )
    (net (code "40") (name "Net-(D6-K)") (class "Default")
      (node (ref "D6") (pin "2") (pinfunction "K_2") (pintype "passive"))
      (node (ref "R22") (pin "1") (pinfunction "1_1") (pintype "passive"))
    )
    (net (code "41") (name "Net-(D7-A)") (class "Default")
      (node (ref "D7") (pin "1") (pinfunction "A_1") (pintype "passive"))
      (node (ref "R23") (pin "1") (pinfunction "1_1") (pintype "passive"))
    )
    (net (code "42") (name "Net-(D8-K)") (class "Default")
      (node (ref "D8") (pin "2") (pinfunction "K_2") (pintype "passive"))
      (node (ref "R24") (pin "1") (pinfunction "1_1") (pintype "passive"))
    )
    (net (code "43") (name "Net-(D9-K)") (class "Default")
      (node (ref "D9") (pin "2") (pinfunction "K_2") (pintype "passive"))
      (node (ref "R25") (pin "1") (pinfunction "1_1") (pintype "passive"))
    )
    (net (code "44") (name "Net-(D10-K)") (class "Default")
      (node (ref "D10") (pin "2") (pinfunction "K_2") (pintype "passive"))
      (node (ref "R26") (pin "1") (pinfunction "1_1") (pintype "passive"))
    )
    (net (code "45") (name "Net-(D11-K)") (class "Default")
      (node (ref "D11") (pin "2") (pinfunction "K_2") (pintype "passive"))
      (node (ref "R27") (pin "1") (pinfunction "1_1") (pintype "passive"))
    )
    (net (code "46") (name "Net-(U4-CAPM)") (class "Default")
      (node (ref "C13") (pin "1") (pinfunction "1_1") (pintype "passive"))
      (node (ref "U4") (pin "4") (pinfunction "CAPM_4") (pintype "input"))
    )
    (net (code "47") (name "Net-(U4-CAPP)") (class "Default")
      (node (ref "C13") (pin "2") (pinfunction "2_2") (pintype "passive"))
      (node (ref "U4") (pin "2") (pinfunction "CAPP_2") (pintype "input"))
    )
    (net (code "48") (name "Net-(U4-LDOO)") (class "Default")
      (node (ref "C14") (pin "1") (pinfunction "1_1") (pintype "passive"))
      (node (ref "C15") (pin "1") (pinfunction "1_1") (pintype "passive"))
      (node (ref "U4") (pin "18") (pinfunction "LDOO_18") (pintype "input"))
    )
    (net (code "49") (name "Net-(U4-OUTL)") (class "Default")
      (node (ref "R8") (pin "1") (pinfunction "1_1") (pintype "passive"))
      (node (ref "U4") (pin "6") (pinfunction "OUTL_6") (pintype "input"))
    )
    (net (code "50") (name "Net-(U4-OUTR)") (class "Default")
      (node (ref "R9") (pin "1") (pinfunction "1_1") (pintype "passive"))
      (node (ref "U4") (pin "7") (pinfunction "OUTR_7") (pintype "input"))
    )
    (net (code "51") (name "Net-(U4-VNEG)") (class "Default")
      (node (ref "C16") (pin "1") (pinfunction "1_1") (pintype "passive"))
      (node (ref "U4") (pin "5") (pinfunction "VNEG_5") (pintype "input"))
    )
    (net (code "52") (name "Net-(U5-LNA_IN)") (class "Default")
      (node (ref "C27") (pin "2") (pinfunction "2_2") (pintype "passive"))
      (node (ref "R10") (pin "1") (pinfunction "1_1") (pintype "passive"))
      (node (ref "U5") (pin "1") (pinfunction "LNA_IN_1") (pintype "passive"))
    )
    (net (code "53") (name "Net-(U6-+OUT_L)") (class "Default")
      (node (ref "P1") (pin "2") (pinfunction "2_2") (pintype "passive"))
      (node (ref "U6") (pin "1") (pinfunction "+OUT_L_1") (pintype "input"))
    )
    (net (code "54") (name "Net-(U6-+OUT_R)") (class "Default")
      (node (ref "P2") (pin "2") (pinfunction "2_2") (pintype "passive"))
      (node (ref "U6") (pin "16") (pinfunction "+OUT_R_16") (pintype "input"))
    )
    (net (code "55") (name "Net-(U6--OUT_L)") (class "Default")
      (node (ref "P1") (pin "1") (pinfunction "1_1") (pintype "passive"))
      (node (ref "U6") (pin "3") (pinfunction "-OUT_L_3") (pintype "input"))
    )
    (net (code "56") (name "Net-(U6--OUT_R)") (class "Default")
      (node (ref "P2") (pin "1") (pinfunction "1_1") (pintype "passive"))
      (node (ref "U6") (pin "14") (pinfunction "-OUT_R_14") (pintype "input"))
    )
    (net (code "57") (name "Net-(U6-VREF)") (class "Default")
      (node (ref "C33") (pin "2") (pinfunction "2_2") (pintype "passive"))
      (node (ref "U6") (pin "8") (pinfunction "VREF_8") (pintype "input"))
    )
    (net (code "58") (name "Net-(U7-IN)") (class "Default")
      (node (ref "C34") (pin "1") (pinfunction "1_1") (pintype "passive"))
      (node (ref "K2") (pin "1") (pinfunction "1_1") (pintype "passive"))
      (node (ref "U7") (pin "3") (pinfunction "IN_3") (pintype "passive"))
    )
    (net (code "59") (name "Net-(U8-IN)") (class "Default")
      (node (ref "C35") (pin "1") (pinfunction "1_1") (pintype "passive"))
      (node (ref "K1") (pin "1") (pinfunction "1_1") (pintype "passive"))
      (node (ref "U8") (pin "3") (pinfunction "IN_3") (pintype "passive"))
    )
    (net (code "60") (name "Net-(U9-IN)") (class "Default")
      (node (ref "C36") (pin "1") (pinfunction "1_1") (pintype "passive"))
      (node (ref "K3") (pin "1") (pinfunction "1_1") (pintype "passive"))
      (node (ref "U9") (pin "3") (pinfunction "IN_3") (pintype "passive"))
    )
    (net (code "61") (name "Net-(U10-IN)") (class "Default")
      (node (ref "C37") (pin "1") (pinfunction "1_1") (pintype "passive"))
      (node (ref "K4") (pin "1") (pinfunction "1_1") (pintype "passive"))
      (node (ref "U10") (pin "3") (pinfunction "IN_3") (pintype "passive"))
    )
    (net (code "62") (name "Net-(U11-IN)") (class "Default")
      (node (ref "C38") (pin "1") (pinfunction "1_1") (pintype "passive"))
      (node (ref "K5") (pin "1") (pinfunction "1_1") (pintype "passive"))
      (node (ref "U11") (pin "3") (pinfunction "IN_3") (pintype "passive"))
    )
    (net (code "63") (name "Net-(U12-IN)") (class "Default")
      (node (ref "C39") (pin "1") (pinfunction "1_1") (pintype "passive"))
      (node (ref "K6") (pin "1") (pinfunction "1_1") (pintype "passive"))
      (node (ref "U12") (pin "3") (pinfunction "IN_3") (pintype "passive"))
    )
    (net (code "64") (name "Net-(U13-IN)") (class "Default")
      (node (ref "C40") (pin "1") (pinfunction "1_1") (pintype "passive"))
      (node (ref "K7") (pin "1") (pinfunction "1_1") (pintype "passive"))
      (node (ref "U13") (pin "3") (pinfunction "IN_3") (pintype "passive"))
    )
    (net (code "65") (name "Net-(U14-IN)") (class "Default")
      (node (ref "C41") (pin "1") (pinfunction "1_1") (pintype "passive"))
      (node (ref "K8") (pin "1") (pinfunction "1_1") (pintype "passive"))
      (node (ref "U14") (pin "3") (pinfunction "IN_3") (pintype "passive"))
    )
    (net (code "66") (name "Net-(usb1-CC1)") (class "Default")
      (node (ref "R5") (pin "1") (pinfunction "1_1") (pintype "passive"))
      (node (ref "usb1") (pin "3") (pinfunction "CC1_3") (pintype "input"))
    )
    (net (code "67") (name "Net-(usb1-CC2)") (class "Default")
      (node (ref "R2") (pin "1") (pinfunction "1_1") (pintype "passive"))
      (node (ref "usb1") (pin "9") (pinfunction "CC2_9") (pintype "input"))
    )
    (net (code "68") (name "unconnected-(*-NC-Pad2)") (class "Default")
      (node (ref "*") (pin "2") (pinfunction "NC_2") (pintype "passive+no_connect"))
    )
    (net (code "69") (name "unconnected-(U1-NC-Pad4)") (class "Default")
      (node (ref "U1") (pin "4") (pinfunction "NC_4") (pintype "passive"))
    )
    (net (code "70") (name "unconnected-(U2-NC-Pad4)") (class "Default")
      (node (ref "U2") (pin "4") (pinfunction "NC_4") (pintype "passive"))
    )
    (net (code "71") (name "unconnected-(U3-NC-Pad4)") (class "Default")
      (node (ref "U3") (pin "4") (pinfunction "NC_4") (pintype "passive"))
    )
    (net (code "72") (name "unconnected-(U5-NC-Pad19)") (class "Default")
      (node (ref "U5") (pin "19") (pinfunction "NC_19") (pintype "passive"))
    )
    (net (code "73") (name "unconnected-(U5-NC-Pad20)") (class "Default")
      (node (ref "U5") (pin "20") (pinfunction "NC_20") (pintype "passive"))
    )
    (net (code "74") (name "unconnected-(U5-NC-Pad21)") (class "Default")
      (node (ref "U5") (pin "21") (pinfunction "NC_21") (pintype "passive"))
    )
    (net (code "75") (name "unconnected-(U5-NC-Pad22)") (class "Default")
      (node (ref "U5") (pin "22") (pinfunction "NC_22") (pintype "passive"))
    )
    (net (code "76") (name "unconnected-(U5-NC-Pad23)") (class "Default")
      (node (ref "U5") (pin "23") (pinfunction "NC_23") (pintype "passive"))
    )
    (net (code "77") (name "unconnected-(U5-NC-Pad24)") (class "Default")
      (node (ref "U5") (pin "24") (pinfunction "NC_24") (pintype "passive"))
    )
    (net (code "78") (name "unconnected-(U7-AHLB-Pad4)") (class "Default")
      (node (ref "U7") (pin "4") (pinfunction "AHLB_4") (pintype "passive"))
    )
    (net (code "79") (name "unconnected-(U7-TOG-Pad6)") (class "Default")
      (node (ref "U7") (pin "6") (pinfunction "TOG_6") (pintype "passive"))
    )
    (net (code "80") (name "unconnected-(U8-TOG-Pad6)") (class "Default")
      (node (ref "U8") (pin "6") (pinfunction "TOG_6") (pintype "passive"))
    )
    (net (code "81") (name "unconnected-(U9-AHLB-Pad4)") (class "Default")
      (node (ref "U9") (pin "4") (pinfunction "AHLB_4") (pintype "passive"))
    )
    (net (code "82") (name "unconnected-(U9-TOG-Pad6)") (class "Default")
      (node (ref "U9") (pin "6") (pinfunction "TOG_6") (pintype "passive"))
    )
    (net (code "83") (name "unconnected-(U10-TOG-Pad6)") (class "Default")
      (node (ref "U10") (pin "6") (pinfunction "TOG_6") (pintype "passive"))
    )
    (net (code "84") (name "unconnected-(U11-AHLB-Pad4)") (class "Default")
      (node (ref "U11") (pin "4") (pinfunction "AHLB_4") (pintype "passive"))
    )
    (net (code "85") (name "unconnected-(U11-TOG-Pad6)") (class "Default")
      (node (ref "U11") (pin "6") (pinfunction "TOG_6") (pintype "passive"))
    )
    (net (code "86") (name "unconnected-(U12-AHLB-Pad4)") (class "Default")
      (node (ref "U12") (pin "4") (pinfunction "AHLB_4") (pintype "passive"))
    )
    (net (code "87") (name "unconnected-(U12-TOG-Pad6)") (class "Default")
      (node (ref "U12") (pin "6") (pinfunction "TOG_6") (pintype "passive"))
    )
    (net (code "88") (name "unconnected-(U13-AHLB-Pad4)") (class "Default")
      (node (ref "U13") (pin "4") (pinfunction "AHLB_4") (pintype "passive"))
    )
    (net (code "89") (name "unconnected-(U13-TOG-Pad6)") (class "Default")
      (node (ref "U13") (pin "6") (pinfunction "TOG_6") (pintype "passive"))
    )
    (net (code "90") (name "unconnected-(U14-AHLB-Pad4)") (class "Default")
      (node (ref "U14") (pin "4") (pinfunction "AHLB_4") (pintype "passive"))
    )
    (net (code "91") (name "unconnected-(U14-TOG-Pad6)") (class "Default")
      (node (ref "U14") (pin "6") (pinfunction "TOG_6") (pintype "passive"))
    )
    (net (code "92") (name "unconnected-(usb1-SBU1-Pad10)") (class "Default")
      (node (ref "usb1") (pin "10") (pinfunction "SBU1_10") (pintype "input+no_connect"))
    )
    (net (code "93") (name "unconnected-(usb1-SBU2-Pad4)") (class "Default")
      (node (ref "usb1") (pin "4") (pinfunction "SBU2_4") (pintype "input+no_connect"))
    )
  )
)
